# NanoMySens-v016.net
KiCad netlist of a schematic drawn in EAGLE
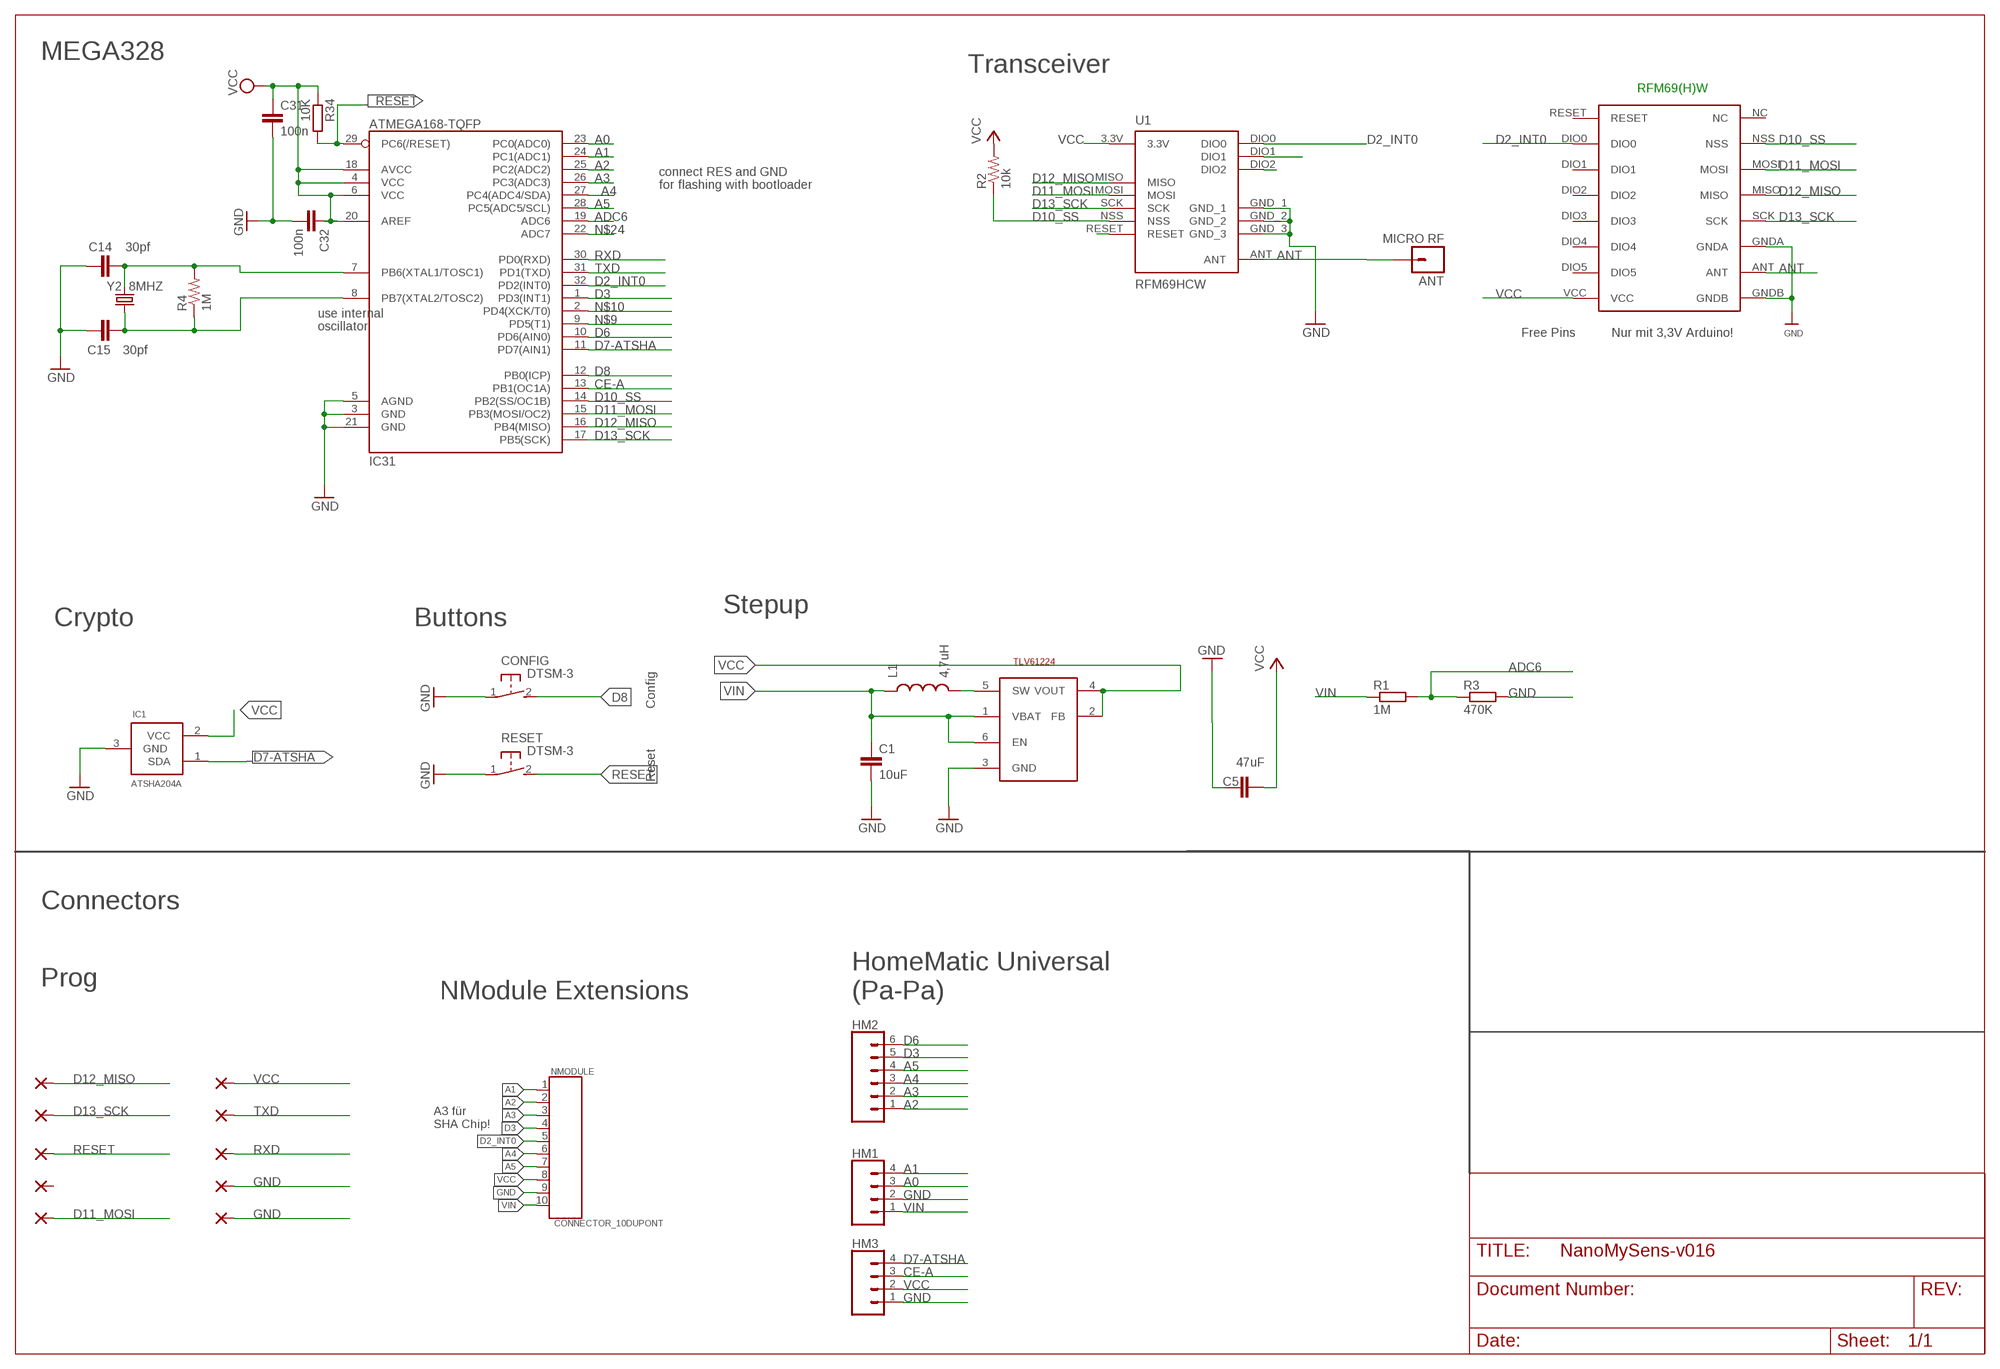
[diagram p0: schematic, sheet 1]

(export (version "E")
  (design (tool "Eeschema 10.0.6"))
  (components
    (comp (ref "ANT")
      (value "MICRO RF")
      (footprint "eagle-import:1X01")
      (libsource (lib "eagle-import") (part "M01PTH"))
    )
    (comp (ref "C1")
      (value "10uF")
      (footprint "eagle-import:0805")
      (libsource (lib "eagle-import") (part "CAP0805"))
    )
    (comp (ref "C5")
      (value "47uF")
      (footprint "eagle-import:C1210")
      (libsource (lib "eagle-import") (part "C-EUC1210"))
    )
    (comp (ref "C14")
      (value "30pf")
      (footprint "eagle-import:0805")
      (libsource (lib "eagle-import") (part "doug_CAP0805"))
    )
    (comp (ref "C15")
      (value "30pf")
      (footprint "eagle-import:0805")
      (libsource (lib "eagle-import") (part "doug_CAP0805"))
    )
    (comp (ref "C31")
      (value "100n")
      (footprint "eagle-import:C0805")
      (libsource (lib "eagle-import") (part "C-EUC0805"))
    )
    (comp (ref "C32")
      (value "100n")
      (footprint "eagle-import:C0805")
      (libsource (lib "eagle-import") (part "C-EUC0805"))
    )
    (comp (ref "CONFIG")
      (value "DTSM-3")
      (footprint "eagle-import:DTSM-3")
      (libsource (lib "eagle-import") (part "DTSM-3"))
    )
    (comp (ref "GND")
      (value "WIREPADSMD1,27-254")
      (footprint "eagle-import:SMD1,27-2,54")
      (libsource (lib "eagle-import") (part "WIREPADSMD1,27-254"))
    )
    (comp (ref "GND2")
      (value "WIREPADSMD1,27-254")
      (footprint "eagle-import:SMD1,27-2,54")
      (libsource (lib "eagle-import") (part "WIREPADSMD1,27-254"))
    )
    (comp (ref "HM1")
      (value "CONN_04")
      (footprint "eagle-import:1X04")
      (libsource (lib "eagle-import") (part "CONN_04"))
    )
    (comp (ref "HM2")
      (value "CONN_06SILK_FEMALE_PTH")
      (footprint "eagle-import:1X06")
      (libsource (lib "eagle-import") (part "CONN_06SILK_FEMALE_PTH"))
    )
    (comp (ref "HM3")
      (value "CONN_04")
      (footprint "eagle-import:1X04")
      (libsource (lib "eagle-import") (part "CONN_04"))
    )
    (comp (ref "IC1")
      (value "ATSHA204A")
      (footprint "eagle-import:SOT23")
      (libsource (lib "eagle-import") (part "ATSHA204A"))
    )
    (comp (ref "IC31")
      (value "ATMEGA168-TQFP")
      (footprint "eagle-import:TQFP32-08")
      (libsource (lib "eagle-import") (part "ATMEGA168-TQFP"))
    )
    (comp (ref "L1")
      (value "4,7uH")
      (footprint "eagle-import:0805")
      (libsource (lib "eagle-import") (part "INDUCTOR0805"))
    )
    (comp (ref "MISO")
      (value "WIREPADSMD1,27-254")
      (footprint "eagle-import:SMD1,27-2,54")
      (libsource (lib "eagle-import") (part "WIREPADSMD1,27-254"))
    )
    (comp (ref "MOSI")
      (value "WIREPADSMD1,27-254")
      (footprint "eagle-import:SMD1,27-2,54")
      (libsource (lib "eagle-import") (part "WIREPADSMD1,27-254"))
    )
    (comp (ref "NC")
      (value "WIREPADSMD1,27-254")
      (footprint "eagle-import:SMD1,27-2,54")
      (libsource (lib "eagle-import") (part "WIREPADSMD1,27-254"))
    )
    (comp (ref "NMODULE")
      (value "CONNECTOR_10DUPONT")
      (footprint "eagle-import:DUPONT_10")
      (libsource (lib "eagle-import") (part "CONNECTOR_10DUPONT"))
    )
    (comp (ref "R1")
      (value "1M")
      (footprint "eagle-import:R0805")
      (libsource (lib "eagle-import") (part "R-EU_R0805"))
    )
    (comp (ref "R2")
      (value "10k")
      (footprint "eagle-import:0805")
      (libsource (lib "eagle-import") (part "RESISTOR0805-RES"))
    )
    (comp (ref "R3")
      (value "470K")
      (footprint "eagle-import:R0805")
      (libsource (lib "eagle-import") (part "R-EU_R0805"))
    )
    (comp (ref "R4")
      (value "1M")
      (footprint "eagle-import:0805")
      (libsource (lib "eagle-import") (part "RESISTOR0805-RES"))
    )
    (comp (ref "R34")
      (value "10K")
      (footprint "eagle-import:R0805")
      (libsource (lib "eagle-import") (part "R-EU_R0805"))
    )
    (comp (ref "RESET")
      (value "DTSM-3")
      (footprint "eagle-import:DTSM-3")
      (libsource (lib "eagle-import") (part "DTSM-3"))
    )
    (comp (ref "RFM69W")
      (value "RFM69HW")
      (footprint "eagle-import:RFM")
      (libsource (lib "eagle-import") (part "RFM69HW"))
    )
    (comp (ref "RST")
      (value "WIREPADSMD1,27-254")
      (footprint "eagle-import:SMD1,27-2,54")
      (libsource (lib "eagle-import") (part "WIREPADSMD1,27-254"))
    )
    (comp (ref "RXD")
      (value "WIREPADSMD1,27-254")
      (footprint "eagle-import:SMD1,27-2,54")
      (libsource (lib "eagle-import") (part "WIREPADSMD1,27-254"))
    )
    (comp (ref "SCK")
      (value "WIREPADSMD1,27-254")
      (footprint "eagle-import:SMD1,27-2,54")
      (libsource (lib "eagle-import") (part "WIREPADSMD1,27-254"))
    )
    (comp (ref "STEPUP")
      (value "TLV61224")
      (footprint "eagle-import:SOT23-6L")
      (libsource (lib "eagle-import") (part "TI-TLV61224"))
    )
    (comp (ref "TXD")
      (value "WIREPADSMD1,27-254")
      (footprint "eagle-import:SMD1,27-2,54")
      (libsource (lib "eagle-import") (part "WIREPADSMD1,27-254"))
    )
    (comp (ref "U1")
      (value "RFM69HCW")
      (footprint "eagle-import:RFM69HCW-XXXS2")
      (libsource (lib "eagle-import") (part "RFM69HCW"))
    )
    (comp (ref "VCC")
      (value "WIREPADSMD1,27-254")
      (footprint "eagle-import:SMD1,27-2,54")
      (libsource (lib "eagle-import") (part "WIREPADSMD1,27-254"))
    )
    (comp (ref "Y2")
      (value "8MHZ")
      (footprint "eagle-import:CRYSTAL-TXC-7A")
      (libsource (lib "eagle-import") (part "CRYSTALTXC-7A"))
    )
  )
  (nets
    (net (code "1") (name "/A0") (class "Default")
      (node (ref "HM1") (pin "3") (pinfunction "3_3") (pintype "passive"))
      (node (ref "IC31") (pin "23") (pinfunction "PC0(ADC0)_23") (pintype "bidirectional"))
    )
    (net (code "2") (name "/ADC6") (class "Default")
      (node (ref "IC31") (pin "19") (pinfunction "ADC6_19") (pintype "bidirectional"))
      (node (ref "R1") (pin "2") (pinfunction "2_2") (pintype "passive"))
      (node (ref "R3") (pin "1") (pinfunction "1_1") (pintype "passive"))
    )
    (net (code "3") (name "/ANT") (class "Default")
      (node (ref "ANT") (pin "1") (pinfunction "1_1") (pintype "passive"))
      (node (ref "RFM69W") (pin "ANT") (pinfunction "ANT_ANT") (pintype "bidirectional"))
      (node (ref "U1") (pin "ANT") (pinfunction "ANT_ANT") (pintype "passive"))
    )
    (net (code "4") (name "/CE-A") (class "Default")
      (node (ref "HM3") (pin "3") (pinfunction "3_3") (pintype "passive"))
      (node (ref "IC31") (pin "13") (pinfunction "PB1(OC1A)_13") (pintype "bidirectional"))
    )
    (net (code "5") (name "/D6") (class "Default")
      (node (ref "HM2") (pin "6") (pinfunction "6_6") (pintype "passive"))
      (node (ref "IC31") (pin "10") (pinfunction "PD6(AIN0)_10") (pintype "bidirectional"))
    )
    (net (code "6") (name "/D7-ATSHA") (class "Default")
      (node (ref "HM3") (pin "4") (pinfunction "4_4") (pintype "passive"))
      (node (ref "IC1") (pin "1") (pinfunction "SDA_1") (pintype "bidirectional"))
      (node (ref "IC31") (pin "11") (pinfunction "PD7(AIN1)_11") (pintype "bidirectional"))
    )
    (net (code "7") (name "/D10_SS") (class "Default")
      (node (ref "IC31") (pin "14") (pinfunction "PB2(SS/OC1B)_14") (pintype "bidirectional"))
      (node (ref "R2") (pin "1") (pinfunction "1_1") (pintype "passive"))
      (node (ref "RFM69W") (pin "NSS") (pinfunction "NSS_NSS") (pintype "bidirectional"))
      (node (ref "U1") (pin "NSS") (pinfunction "NSS_NSS") (pintype "input"))
    )
    (net (code "8") (name "/D11_MOSI") (class "Default")
      (node (ref "IC31") (pin "15") (pinfunction "PB3(MOSI/OC2)_15") (pintype "bidirectional"))
      (node (ref "MOSI") (pin "1") (pinfunction "P_1") (pintype "passive"))
      (node (ref "RFM69W") (pin "MOSI") (pinfunction "MOSI_MOSI") (pintype "bidirectional"))
      (node (ref "U1") (pin "MOSI") (pinfunction "MOSI_MOSI") (pintype "input"))
    )
    (net (code "9") (name "/D12_MISO") (class "Default")
      (node (ref "IC31") (pin "16") (pinfunction "PB4(MISO)_16") (pintype "bidirectional"))
      (node (ref "MISO") (pin "1") (pinfunction "P_1") (pintype "passive"))
      (node (ref "RFM69W") (pin "MISO") (pinfunction "MISO_MISO") (pintype "bidirectional"))
      (node (ref "U1") (pin "MISO") (pinfunction "MISO_MISO") (pintype "bidirectional"))
    )
    (net (code "10") (name "/D13_SCK") (class "Default")
      (node (ref "IC31") (pin "17") (pinfunction "PB5(SCK)_17") (pintype "bidirectional"))
      (node (ref "RFM69W") (pin "SCK") (pinfunction "SCK_SCK") (pintype "bidirectional"))
      (node (ref "SCK") (pin "1") (pinfunction "P_1") (pintype "passive"))
      (node (ref "U1") (pin "SCK") (pinfunction "SCK_SCK") (pintype "input"))
    )
    (net (code "11") (name "/N$9") (class "Default")
      (node (ref "IC31") (pin "9") (pinfunction "PD5(T1)_9") (pintype "bidirectional"))
    )
    (net (code "12") (name "/N$10") (class "Default")
      (node (ref "IC31") (pin "2") (pinfunction "PD4(XCK/T0)_2") (pintype "bidirectional"))
    )
    (net (code "13") (name "/N$24") (class "Default")
      (node (ref "IC31") (pin "22") (pinfunction "ADC7_22") (pintype "bidirectional"))
    )
    (net (code "14") (name "/RXD") (class "Default")
      (node (ref "IC31") (pin "30") (pinfunction "PD0(RXD)_30") (pintype "bidirectional"))
      (node (ref "RXD") (pin "1") (pinfunction "P_1") (pintype "passive"))
    )
    (net (code "15") (name "/TXD") (class "Default")
      (node (ref "IC31") (pin "31") (pinfunction "PD1(TXD)_31") (pintype "bidirectional"))
      (node (ref "TXD") (pin "1") (pinfunction "P_1") (pintype "passive"))
    )
    (net (code "16") (name "A1") (class "Default")
      (node (ref "HM1") (pin "4") (pinfunction "4_4") (pintype "passive"))
      (node (ref "IC31") (pin "24") (pinfunction "PC1(ADC1)_24") (pintype "bidirectional"))
      (node (ref "NMODULE") (pin "1") (pinfunction "1_1") (pintype "bidirectional"))
    )
    (net (code "17") (name "A2") (class "Default")
      (node (ref "HM2") (pin "1") (pinfunction "1_1") (pintype "passive"))
      (node (ref "IC31") (pin "25") (pinfunction "PC2(ADC2)_25") (pintype "bidirectional"))
      (node (ref "NMODULE") (pin "2") (pinfunction "2_2") (pintype "bidirectional"))
    )
    (net (code "18") (name "A3") (class "Default")
      (node (ref "HM2") (pin "2") (pinfunction "2_2") (pintype "passive"))
      (node (ref "IC31") (pin "26") (pinfunction "PC3(ADC3)_26") (pintype "bidirectional"))
      (node (ref "NMODULE") (pin "3") (pinfunction "3_3") (pintype "bidirectional"))
    )
    (net (code "19") (name "A4") (class "Default")
      (node (ref "HM2") (pin "3") (pinfunction "3_3") (pintype "passive"))
      (node (ref "IC31") (pin "27") (pinfunction "PC4(ADC4/SDA)_27") (pintype "bidirectional"))
      (node (ref "NMODULE") (pin "6") (pinfunction "6_6") (pintype "bidirectional"))
    )
    (net (code "20") (name "A5") (class "Default")
      (node (ref "HM2") (pin "4") (pinfunction "4_4") (pintype "passive"))
      (node (ref "IC31") (pin "28") (pinfunction "PC5(ADC5/SCL)_28") (pintype "bidirectional"))
      (node (ref "NMODULE") (pin "7") (pinfunction "7_7") (pintype "bidirectional"))
    )
    (net (code "21") (name "D2_INT0") (class "Default")
      (node (ref "IC31") (pin "32") (pinfunction "PD2(INT0)_32") (pintype "bidirectional"))
      (node (ref "NMODULE") (pin "5") (pinfunction "5_5") (pintype "bidirectional"))
      (node (ref "RFM69W") (pin "DIO0") (pinfunction "DIO0_DIO0") (pintype "bidirectional"))
      (node (ref "U1") (pin "DIO0") (pinfunction "DIO0_DIO0") (pintype "bidirectional"))
    )
    (net (code "22") (name "D3") (class "Default")
      (node (ref "HM2") (pin "5") (pinfunction "5_5") (pintype "passive"))
      (node (ref "IC31") (pin "1") (pinfunction "PD3(INT1)_1") (pintype "bidirectional"))
      (node (ref "NMODULE") (pin "4") (pinfunction "4_4") (pintype "bidirectional"))
    )
    (net (code "23") (name "D8") (class "Default")
      (node (ref "CONFIG") (pin "2") (pinfunction "2_2") (pintype "passive"))
      (node (ref "IC31") (pin "12") (pinfunction "PB0(ICP)_12") (pintype "bidirectional"))
    )
    (net (code "24") (name "GND") (class "Default")
      (node (ref "C1") (pin "2") (pinfunction "2_2") (pintype "passive"))
      (node (ref "C14") (pin "1") (pinfunction "1_1") (pintype "passive"))
      (node (ref "C15") (pin "1") (pinfunction "1_1") (pintype "passive"))
      (node (ref "C31") (pin "2") (pinfunction "2_2") (pintype "passive"))
      (node (ref "C32") (pin "2") (pinfunction "2_2") (pintype "passive"))
      (node (ref "C5") (pin "1") (pinfunction "1_1") (pintype "passive"))
      (node (ref "CONFIG") (pin "1") (pinfunction "1_1") (pintype "passive"))
      (node (ref "GND") (pin "1") (pinfunction "P_1") (pintype "passive"))
      (node (ref "GND2") (pin "1") (pinfunction "P_1") (pintype "passive"))
      (node (ref "HM1") (pin "2") (pinfunction "2_2") (pintype "passive"))
      (node (ref "HM3") (pin "1") (pinfunction "1_1") (pintype "passive"))
      (node (ref "IC1") (pin "3") (pinfunction "GND_3") (pintype "bidirectional"))
      (node (ref "IC31") (pin "21") (pinfunction "GND_21") (pintype "bidirectional"))
      (node (ref "IC31") (pin "3") (pinfunction "GND_3") (pintype "bidirectional"))
      (node (ref "IC31") (pin "5") (pinfunction "AGND_5") (pintype "bidirectional"))
      (node (ref "NMODULE") (pin "9") (pinfunction "9_9") (pintype "bidirectional"))
      (node (ref "R3") (pin "2") (pinfunction "2_2") (pintype "passive"))
      (node (ref "RESET") (pin "1") (pinfunction "1_1") (pintype "passive"))
      (node (ref "RFM69W") (pin "GNDA") (pinfunction "GNDA_GNDA") (pintype "bidirectional"))
      (node (ref "RFM69W") (pin "GNDB") (pinfunction "GNDB_GNDB") (pintype "bidirectional"))
      (node (ref "STEPUP") (pin "3") (pinfunction "GND_3") (pintype "power_in"))
      (node (ref "U1") (pin "GND_1") (pinfunction "GND_1_GND_1") (pintype "power_in"))
      (node (ref "U1") (pin "GND_2") (pinfunction "GND_2_GND_2") (pintype "power_in"))
      (node (ref "U1") (pin "GND_3") (pinfunction "GND_3_GND_3") (pintype "power_in"))
    )
    (net (code "25") (name "Net-(IC31-PB6(XTAL1{slash}TOSC1))") (class "Default")
      (node (ref "C14") (pin "2") (pinfunction "2_2") (pintype "passive"))
      (node (ref "IC31") (pin "7") (pinfunction "PB6(XTAL1/TOSC1)_7") (pintype "bidirectional"))
      (node (ref "R4") (pin "2") (pinfunction "2_2") (pintype "passive"))
      (node (ref "Y2") (pin "P$2") (pinfunction "2_P$2") (pintype "passive"))
    )
    (net (code "26") (name "Net-(IC31-PB7(XTAL2{slash}TOSC2))") (class "Default")
      (node (ref "C15") (pin "2") (pinfunction "2_2") (pintype "passive"))
      (node (ref "IC31") (pin "8") (pinfunction "PB7(XTAL2/TOSC2)_8") (pintype "bidirectional"))
      (node (ref "R4") (pin "1") (pinfunction "1_1") (pintype "passive"))
      (node (ref "Y2") (pin "P$1") (pinfunction "1_P$1") (pintype "passive"))
    )
    (net (code "27") (name "Net-(STEPUP-SW)") (class "Default")
      (node (ref "L1") (pin "2") (pinfunction "2_2") (pintype "passive"))
      (node (ref "STEPUP") (pin "5") (pinfunction "SW_5") (pintype "power_in"))
    )
    (net (code "28") (name "RESET") (class "Default")
      (node (ref "IC31") (pin "29") (pinfunction "PC6(/RESET)_29") (pintype "bidirectional"))
      (node (ref "R34") (pin "2") (pinfunction "2_2") (pintype "passive"))
      (node (ref "RESET") (pin "2") (pinfunction "2_2") (pintype "passive"))
      (node (ref "RST") (pin "1") (pinfunction "P_1") (pintype "passive"))
    )
    (net (code "29") (name "VCC") (class "Default")
      (node (ref "C31") (pin "1") (pinfunction "1_1") (pintype "passive"))
      (node (ref "C32") (pin "1") (pinfunction "1_1") (pintype "passive"))
      (node (ref "C5") (pin "2") (pinfunction "2_2") (pintype "passive"))
      (node (ref "HM3") (pin "2") (pinfunction "2_2") (pintype "passive"))
      (node (ref "IC1") (pin "2") (pinfunction "VCC_2") (pintype "bidirectional"))
      (node (ref "IC31") (pin "18") (pinfunction "AVCC_18") (pintype "bidirectional"))
      (node (ref "IC31") (pin "20") (pinfunction "AREF_20") (pintype "bidirectional"))
      (node (ref "IC31") (pin "4") (pinfunction "VCC_4") (pintype "bidirectional"))
      (node (ref "IC31") (pin "6") (pinfunction "VCC_6") (pintype "bidirectional"))
      (node (ref "NMODULE") (pin "8") (pinfunction "8_8") (pintype "bidirectional"))
      (node (ref "R2") (pin "2") (pinfunction "2_2") (pintype "passive"))
      (node (ref "R34") (pin "1") (pinfunction "1_1") (pintype "passive"))
      (node (ref "RFM69W") (pin "VCC") (pinfunction "VCC_VCC") (pintype "bidirectional"))
      (node (ref "STEPUP") (pin "2") (pinfunction "FB_2") (pintype "input"))
      (node (ref "STEPUP") (pin "4") (pinfunction "VOUT_4") (pintype "power_in"))
      (node (ref "U1") (pin "3.3V") (pinfunction "3.3V_3.3V") (pintype "power_in"))
      (node (ref "VCC") (pin "1") (pinfunction "P_1") (pintype "passive"))
    )
    (net (code "30") (name "VIN") (class "Default")
      (node (ref "C1") (pin "1") (pinfunction "1_1") (pintype "passive"))
      (node (ref "HM1") (pin "1") (pinfunction "1_1") (pintype "passive"))
      (node (ref "L1") (pin "1") (pinfunction "1_1") (pintype "passive"))
      (node (ref "NMODULE") (pin "10") (pinfunction "10_10") (pintype "bidirectional"))
      (node (ref "R1") (pin "1") (pinfunction "1_1") (pintype "passive"))
      (node (ref "STEPUP") (pin "1") (pinfunction "VBAT_1") (pintype "power_in"))
      (node (ref "STEPUP") (pin "6") (pinfunction "EN_6") (pintype "input"))
    )
    (net (code "31") (name "unconnected-(NC-P-Pad1)") (class "Default")
      (node (ref "NC") (pin "1") (pinfunction "P_1") (pintype "passive"))
    )
    (net (code "32") (name "unconnected-(RFM69W-PadDIO1)") (class "Default")
      (node (ref "RFM69W") (pin "DIO1") (pinfunction "DIO1_DIO1") (pintype "bidirectional"))
    )
    (net (code "33") (name "unconnected-(RFM69W-PadDIO2)") (class "Default")
      (node (ref "RFM69W") (pin "DIO2") (pinfunction "DIO2_DIO2") (pintype "bidirectional"))
    )
    (net (code "34") (name "unconnected-(RFM69W-PadDIO3)") (class "Default")
      (node (ref "RFM69W") (pin "DIO3") (pinfunction "DIO3_DIO3") (pintype "bidirectional"))
    )
    (net (code "35") (name "unconnected-(RFM69W-PadDIO4)") (class "Default")
      (node (ref "RFM69W") (pin "DIO4") (pinfunction "DIO4_DIO4") (pintype "bidirectional"))
    )
    (net (code "36") (name "unconnected-(RFM69W-PadDIO5)") (class "Default")
      (node (ref "RFM69W") (pin "DIO5") (pinfunction "DIO5_DIO5") (pintype "bidirectional"))
    )
    (net (code "37") (name "unconnected-(RFM69W-PadNC)") (class "Default")
      (node (ref "RFM69W") (pin "NC") (pinfunction "NC_NC") (pintype "bidirectional"))
    )
    (net (code "38") (name "unconnected-(RFM69W-PadRESET)") (class "Default")
      (node (ref "RFM69W") (pin "RESET") (pinfunction "RESET_RESET") (pintype "bidirectional"))
    )
    (net (code "39") (name "unconnected-(U1-PadDIO1)") (class "Default")
      (node (ref "U1") (pin "DIO1") (pinfunction "DIO1_DIO1") (pintype "bidirectional"))
    )
    (net (code "40") (name "unconnected-(U1-PadDIO2)") (class "Default")
      (node (ref "U1") (pin "DIO2") (pinfunction "DIO2_DIO2") (pintype "bidirectional"))
    )
    (net (code "41") (name "unconnected-(U1-PadRESET)") (class "Default")
      (node (ref "U1") (pin "RESET") (pinfunction "RESET_RESET") (pintype "input"))
    )
  )
)
